# Pg3-Voltage_signal_condtioning.net
KiCad netlist of a schematic drawn in Altium Designer
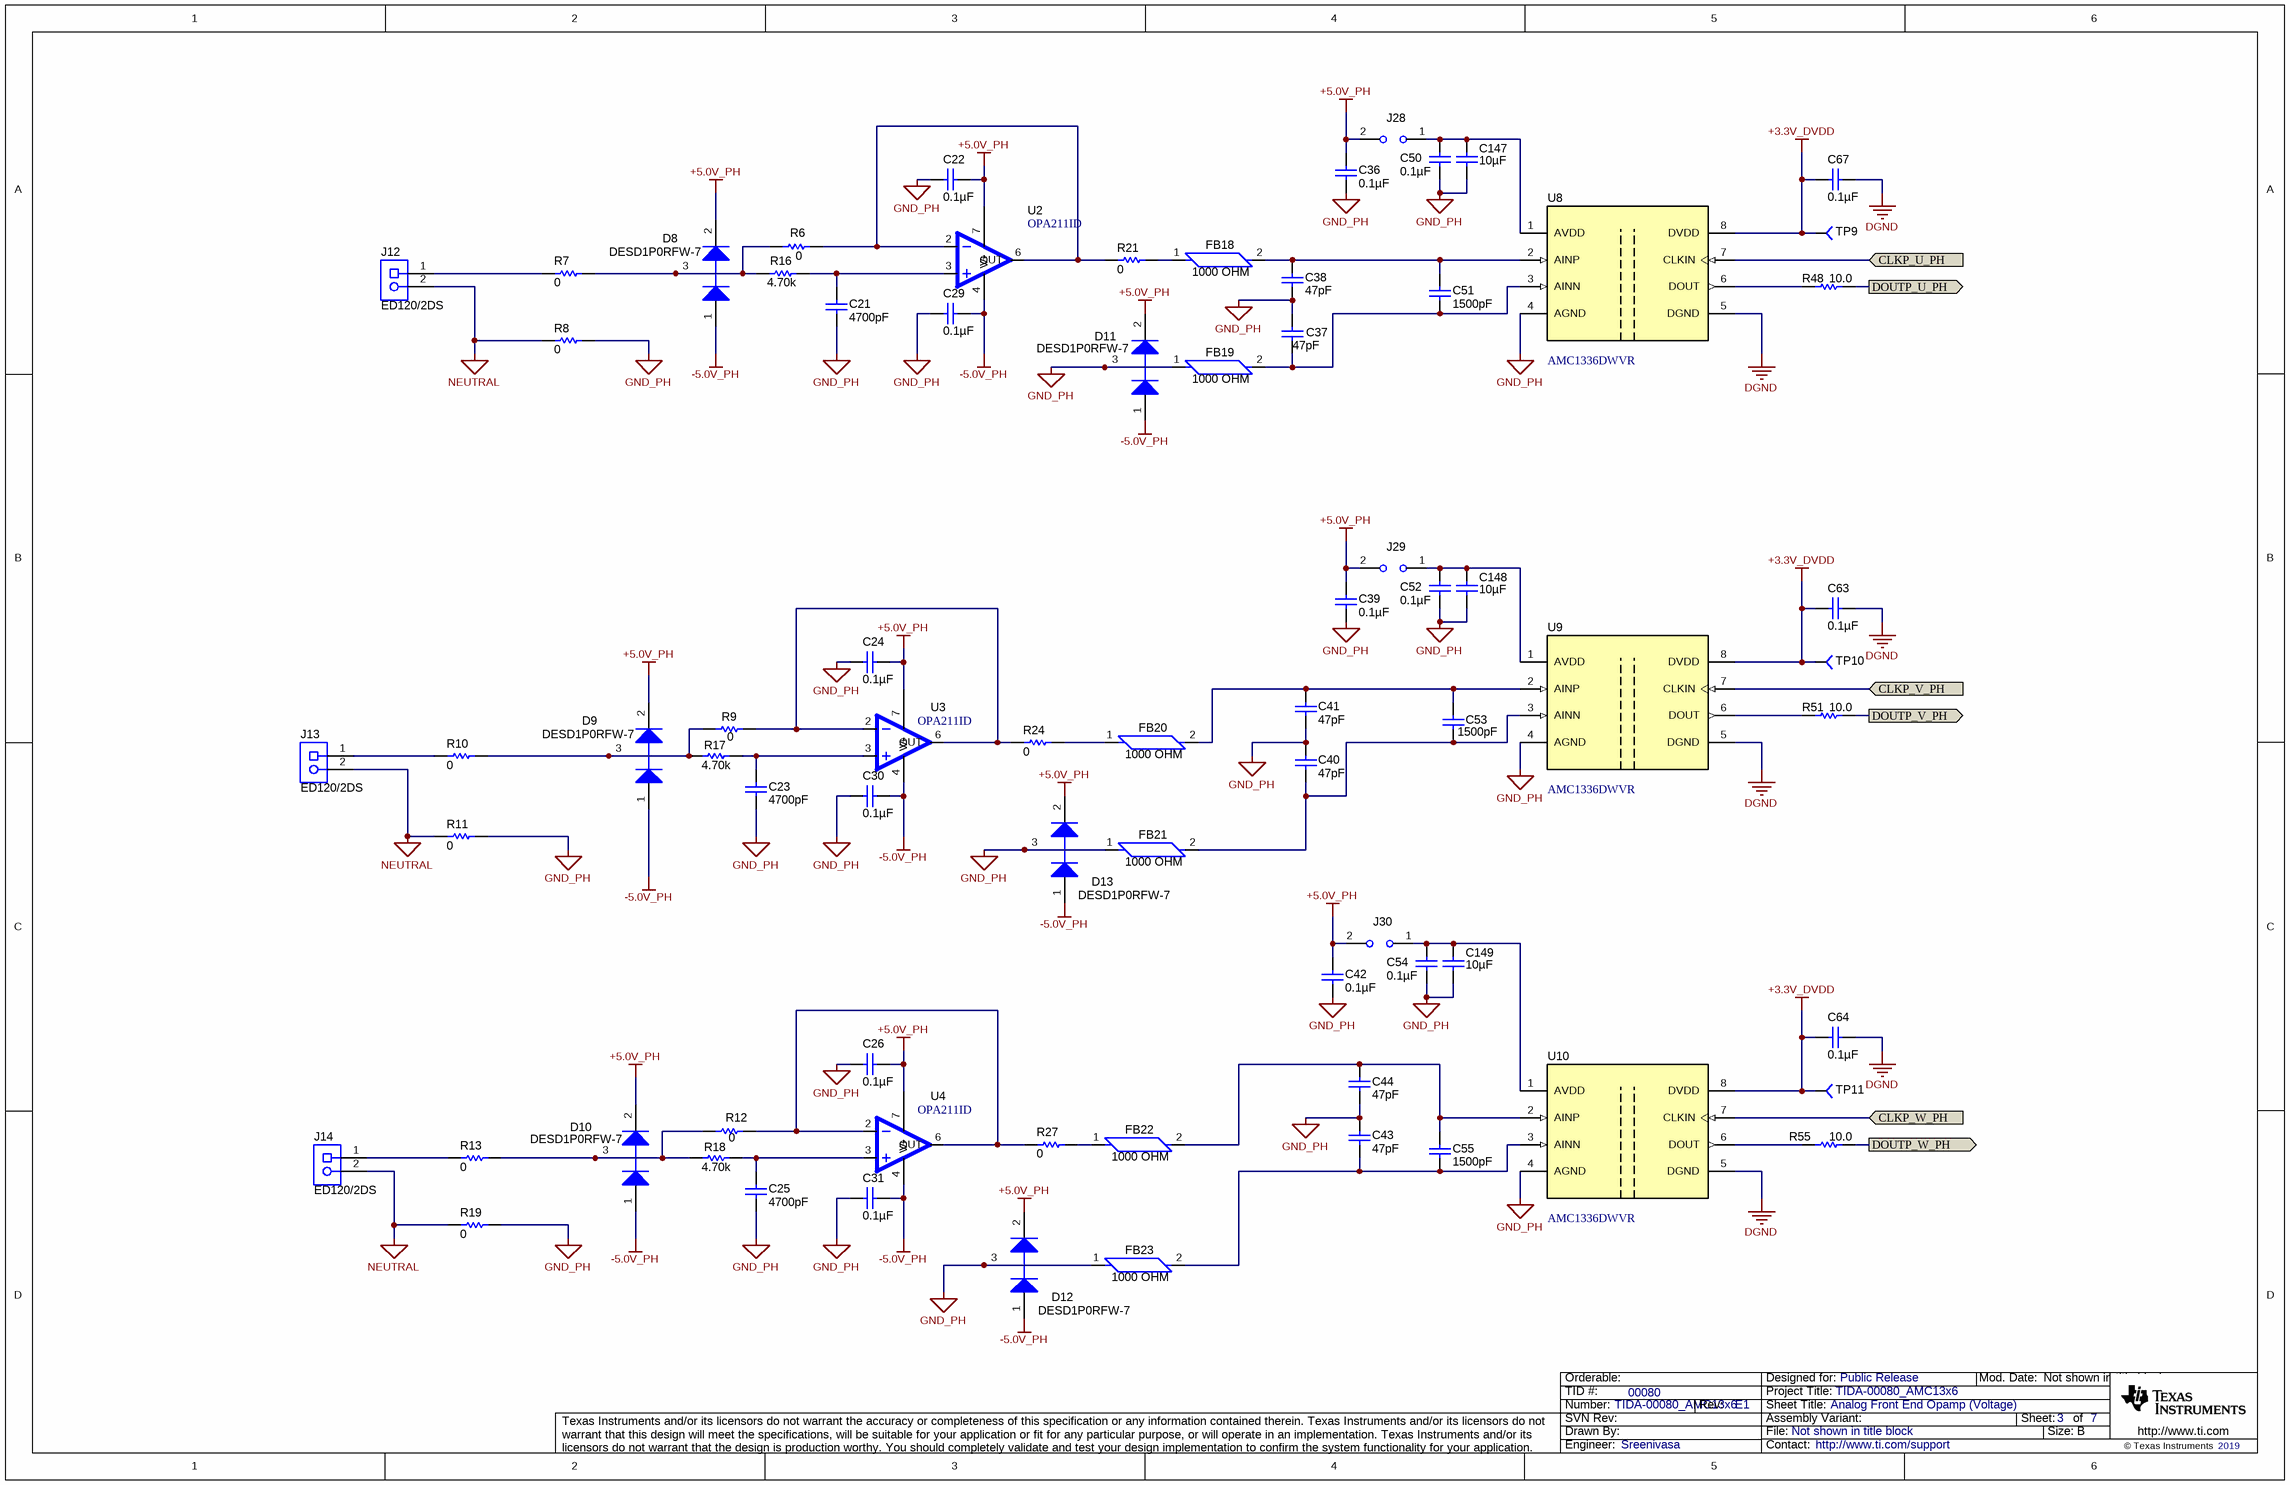
[diagram p0: Pg3-Voltage signal condtioning.SchDoc]

(export (version "E")
  (design (tool "Eeschema 10.0.6"))
  (components
    (comp (ref "C21")
      (value "~")
      (footprint "ISE_MCS_SDM_E1_20MAY:0603")
      (description "CAP, CERM, 4700pF, 100V, +/-10%, X7R, 0603")
      (fields
        (field (name "PARTNUMBER") "06031C472KAT2A")
        (field (name "VALUEDISPLAYED") "4700pF")
        (field (name "MANUFACTURER") "AVX")
        (field (name "PUBLISHER") "Texas Instruments")
      )
      (libsource (lib "Capacitor_Ceramic") (part "06031C472KAT2A"))
    )
    (comp (ref "C22")
      (value "~")
      (footprint "ISE_MCS_SDM_E1_20MAY:0603")
      (description "CAP, CERM, 0.1uF, 50V, +/-10%, X7R, 0603")
      (fields
        (field (name "PARTNUMBER") "C0603C104K5RACTU")
        (field (name "VALUEDISPLAYED") "0.1µF")
        (field (name "MANUFACTURER") "Kemet")
        (field (name "PUBLISHER") "Texas Instruments")
      )
      (libsource (lib "Capacitor_Ceramic") (part "C0603C104K5RACTU"))
    )
    (comp (ref "C23")
      (value "~")
      (footprint "ISE_MCS_SDM_E1_20MAY:0603")
      (description "CAP, CERM, 4700pF, 100V, +/-10%, X7R, 0603")
      (fields
        (field (name "PARTNUMBER") "06031C472KAT2A")
        (field (name "VALUEDISPLAYED") "4700pF")
        (field (name "MANUFACTURER") "AVX")
        (field (name "PUBLISHER") "Texas Instruments")
      )
      (libsource (lib "Capacitor_Ceramic") (part "06031C472KAT2A"))
    )
    (comp (ref "C24")
      (value "~")
      (footprint "ISE_MCS_SDM_E1_20MAY:0603")
      (description "CAP, CERM, 0.1uF, 50V, +/-10%, X7R, 0603")
      (fields
        (field (name "PARTNUMBER") "C0603C104K5RACTU")
        (field (name "VALUEDISPLAYED") "0.1µF")
        (field (name "MANUFACTURER") "Kemet")
        (field (name "PUBLISHER") "Texas Instruments")
      )
      (libsource (lib "Capacitor_Ceramic") (part "C0603C104K5RACTU"))
    )
    (comp (ref "C25")
      (value "~")
      (footprint "ISE_MCS_SDM_E1_20MAY:0603")
      (description "CAP, CERM, 4700pF, 100V, +/-10%, X7R, 0603")
      (fields
        (field (name "PARTNUMBER") "06031C472KAT2A")
        (field (name "VALUEDISPLAYED") "4700pF")
        (field (name "MANUFACTURER") "AVX")
        (field (name "PUBLISHER") "Texas Instruments")
      )
      (libsource (lib "Capacitor_Ceramic") (part "06031C472KAT2A"))
    )
    (comp (ref "C26")
      (value "~")
      (footprint "ISE_MCS_SDM_E1_20MAY:0603")
      (description "CAP, CERM, 0.1uF, 50V, +/-10%, X7R, 0603")
      (fields
        (field (name "PARTNUMBER") "C0603C104K5RACTU")
        (field (name "VALUEDISPLAYED") "0.1µF")
        (field (name "MANUFACTURER") "Kemet")
        (field (name "PUBLISHER") "Texas Instruments")
      )
      (libsource (lib "Capacitor_Ceramic") (part "C0603C104K5RACTU"))
    )
    (comp (ref "C29")
      (value "~")
      (footprint "ISE_MCS_SDM_E1_20MAY:0603")
      (description "CAP, CERM, 0.1uF, 50V, +/-10%, X7R, 0603")
      (fields
        (field (name "PARTNUMBER") "C0603C104K5RACTU")
        (field (name "VALUEDISPLAYED") "0.1µF")
        (field (name "MANUFACTURER") "Kemet")
        (field (name "PUBLISHER") "Texas Instruments")
      )
      (libsource (lib "Capacitor_Ceramic") (part "C0603C104K5RACTU"))
    )
    (comp (ref "C30")
      (value "~")
      (footprint "ISE_MCS_SDM_E1_20MAY:0603")
      (description "CAP, CERM, 0.1uF, 50V, +/-10%, X7R, 0603")
      (fields
        (field (name "PARTNUMBER") "C0603C104K5RACTU")
        (field (name "VALUEDISPLAYED") "0.1µF")
        (field (name "MANUFACTURER") "Kemet")
        (field (name "PUBLISHER") "Texas Instruments")
      )
      (libsource (lib "Capacitor_Ceramic") (part "C0603C104K5RACTU"))
    )
    (comp (ref "C31")
      (value "~")
      (footprint "ISE_MCS_SDM_E1_20MAY:0603")
      (description "CAP, CERM, 0.1uF, 50V, +/-10%, X7R, 0603")
      (fields
        (field (name "PARTNUMBER") "C0603C104K5RACTU")
        (field (name "VALUEDISPLAYED") "0.1µF")
        (field (name "MANUFACTURER") "Kemet")
        (field (name "PUBLISHER") "Texas Instruments")
      )
      (libsource (lib "Capacitor_Ceramic") (part "C0603C104K5RACTU"))
    )
    (comp (ref "C36")
      (value "~")
      (footprint "ISE_MCS_SDM_E1_20MAY:0603")
      (description "CAP, CERM, 0.1uF, 50V, +/-10%, X7R, 0603")
      (fields
        (field (name "PARTNUMBER") "C0603C104K5RACTU")
        (field (name "VALUEDISPLAYED") "0.1µF")
        (field (name "MANUFACTURER") "Kemet")
        (field (name "PUBLISHER") "Texas Instruments")
      )
      (libsource (lib "Capacitor_Ceramic") (part "C0603C104K5RACTU"))
    )
    (comp (ref "C37")
      (value "GRM21A5C2E470JW01D")
      (footprint "ISE_MCS_SDM_E1_20MAY:0805_HV")
      (description "CAP, CERM, 47pF, 500V, +/-5%, C0G/NP0, 0805")
      (fields
        (field (name "VALUEDISPLAYED") "47pF")
        (field (name "MANUFACTURER") "MuRata")
        (field (name "PUBLISHER") "Texas Instruments")
      )
      (libsource (lib "Capacitor_Ceramic") (part "GRM21A5C2E470JW01D"))
    )
    (comp (ref "C38")
      (value "GRM21A5C2E470JW01D")
      (footprint "ISE_MCS_SDM_E1_20MAY:0805_HV")
      (description "CAP, CERM, 47pF, 500V, +/-5%, C0G/NP0, 0805")
      (fields
        (field (name "VALUEDISPLAYED") "47pF")
        (field (name "MANUFACTURER") "MuRata")
        (field (name "PUBLISHER") "Texas Instruments")
      )
      (libsource (lib "Capacitor_Ceramic") (part "GRM21A5C2E470JW01D"))
    )
    (comp (ref "C39")
      (value "~")
      (footprint "ISE_MCS_SDM_E1_20MAY:0603")
      (description "CAP, CERM, 0.1uF, 50V, +/-10%, X7R, 0603")
      (fields
        (field (name "PARTNUMBER") "C0603C104K5RACTU")
        (field (name "VALUEDISPLAYED") "0.1µF")
        (field (name "MANUFACTURER") "Kemet")
        (field (name "PUBLISHER") "Texas Instruments")
      )
      (libsource (lib "Capacitor_Ceramic") (part "C0603C104K5RACTU"))
    )
    (comp (ref "C40")
      (value "GRM21A5C2E470JW01D")
      (footprint "ISE_MCS_SDM_E1_20MAY:0805_HV")
      (description "CAP, CERM, 47pF, 500V, +/-5%, C0G/NP0, 0805")
      (fields
        (field (name "VALUEDISPLAYED") "47pF")
        (field (name "MANUFACTURER") "MuRata")
        (field (name "PUBLISHER") "Texas Instruments")
      )
      (libsource (lib "Capacitor_Ceramic") (part "GRM21A5C2E470JW01D"))
    )
    (comp (ref "C41")
      (value "GRM21A5C2E470JW01D")
      (footprint "ISE_MCS_SDM_E1_20MAY:0805_HV")
      (description "CAP, CERM, 47pF, 500V, +/-5%, C0G/NP0, 0805")
      (fields
        (field (name "VALUEDISPLAYED") "47pF")
        (field (name "MANUFACTURER") "MuRata")
        (field (name "PUBLISHER") "Texas Instruments")
      )
      (libsource (lib "Capacitor_Ceramic") (part "GRM21A5C2E470JW01D"))
    )
    (comp (ref "C42")
      (value "~")
      (footprint "ISE_MCS_SDM_E1_20MAY:0603")
      (description "CAP, CERM, 0.1uF, 50V, +/-10%, X7R, 0603")
      (fields
        (field (name "PARTNUMBER") "C0603C104K5RACTU")
        (field (name "VALUEDISPLAYED") "0.1µF")
        (field (name "MANUFACTURER") "Kemet")
        (field (name "PUBLISHER") "Texas Instruments")
      )
      (libsource (lib "Capacitor_Ceramic") (part "C0603C104K5RACTU"))
    )
    (comp (ref "C43")
      (value "GRM21A5C2E470JW01D")
      (footprint "ISE_MCS_SDM_E1_20MAY:0805_HV")
      (description "CAP, CERM, 47pF, 500V, +/-5%, C0G/NP0, 0805")
      (fields
        (field (name "VALUEDISPLAYED") "47pF")
        (field (name "MANUFACTURER") "MuRata")
        (field (name "PUBLISHER") "Texas Instruments")
      )
      (libsource (lib "Capacitor_Ceramic") (part "GRM21A5C2E470JW01D"))
    )
    (comp (ref "C44")
      (value "GRM21A5C2E470JW01D")
      (footprint "ISE_MCS_SDM_E1_20MAY:0805_HV")
      (description "CAP, CERM, 47pF, 500V, +/-5%, C0G/NP0, 0805")
      (fields
        (field (name "VALUEDISPLAYED") "47pF")
        (field (name "MANUFACTURER") "MuRata")
        (field (name "PUBLISHER") "Texas Instruments")
      )
      (libsource (lib "Capacitor_Ceramic") (part "GRM21A5C2E470JW01D"))
    )
    (comp (ref "C50")
      (value "~")
      (footprint "ISE_MCS_SDM_E1_20MAY:0603")
      (description "CAP, CERM, 0.1uF, 50V, +/-10%, X7R, 0603")
      (fields
        (field (name "PARTNUMBER") "C0603C104K5RACTU")
        (field (name "VALUEDISPLAYED") "0.1µF")
        (field (name "MANUFACTURER") "Kemet")
        (field (name "PUBLISHER") "Texas Instruments")
      )
      (libsource (lib "Capacitor_Ceramic") (part "C0603C104K5RACTU"))
    )
    (comp (ref "C51")
      (value "06031C152KAT2A")
      (footprint "ISE_MCS_SDM_E1_20MAY:0603")
      (description "CAP, CERM, 1500pF, 100V, +/-10%, X7R, 0603")
      (fields
        (field (name "VALUEDISPLAYED") "1500pF")
        (field (name "MANUFACTURER") "AVX")
        (field (name "PUBLISHER") "Texas Instruments")
      )
      (libsource (lib "Capacitor_Ceramic") (part "06031C152KAT2A"))
    )
    (comp (ref "C52")
      (value "~")
      (footprint "ISE_MCS_SDM_E1_20MAY:0603")
      (description "CAP, CERM, 0.1uF, 50V, +/-10%, X7R, 0603")
      (fields
        (field (name "PARTNUMBER") "C0603C104K5RACTU")
        (field (name "VALUEDISPLAYED") "0.1µF")
        (field (name "MANUFACTURER") "Kemet")
        (field (name "PUBLISHER") "Texas Instruments")
      )
      (libsource (lib "Capacitor_Ceramic") (part "C0603C104K5RACTU"))
    )
    (comp (ref "C53")
      (value "06031C152KAT2A")
      (footprint "ISE_MCS_SDM_E1_20MAY:0603")
      (description "CAP, CERM, 1500pF, 100V, +/-10%, X7R, 0603")
      (fields
        (field (name "VALUEDISPLAYED") "1500pF")
        (field (name "MANUFACTURER") "AVX")
        (field (name "PUBLISHER") "Texas Instruments")
      )
      (libsource (lib "Capacitor_Ceramic") (part "06031C152KAT2A"))
    )
    (comp (ref "C54")
      (value "~")
      (footprint "ISE_MCS_SDM_E1_20MAY:0603")
      (description "CAP, CERM, 0.1uF, 50V, +/-10%, X7R, 0603")
      (fields
        (field (name "PARTNUMBER") "C0603C104K5RACTU")
        (field (name "VALUEDISPLAYED") "0.1µF")
        (field (name "MANUFACTURER") "Kemet")
        (field (name "PUBLISHER") "Texas Instruments")
      )
      (libsource (lib "Capacitor_Ceramic") (part "C0603C104K5RACTU"))
    )
    (comp (ref "C55")
      (value "06031C152KAT2A")
      (footprint "ISE_MCS_SDM_E1_20MAY:0603")
      (description "CAP, CERM, 1500pF, 100V, +/-10%, X7R, 0603")
      (fields
        (field (name "VALUEDISPLAYED") "1500pF")
        (field (name "MANUFACTURER") "AVX")
        (field (name "PUBLISHER") "Texas Instruments")
      )
      (libsource (lib "Capacitor_Ceramic") (part "06031C152KAT2A"))
    )
    (comp (ref "C63")
      (value "~")
      (footprint "ISE_MCS_SDM_E1_20MAY:0603")
      (description "CAP, CERM, 0.1uF, 25V, +/-5%, X7R, 0603")
      (fields
        (field (name "PARTNUMBER") "06033C104JAT2A")
        (field (name "VALUEDISPLAYED") "0.1µF")
        (field (name "MANUFACTURER") "AVX")
        (field (name "PUBLISHER") "Texas Instruments")
      )
      (libsource (lib "Capacitor_Ceramic") (part "06033C104JAT2A"))
    )
    (comp (ref "C64")
      (value "~")
      (footprint "ISE_MCS_SDM_E1_20MAY:0603")
      (description "CAP, CERM, 0.1uF, 25V, +/-5%, X7R, 0603")
      (fields
        (field (name "PARTNUMBER") "06033C104JAT2A")
        (field (name "VALUEDISPLAYED") "0.1µF")
        (field (name "MANUFACTURER") "AVX")
        (field (name "PUBLISHER") "Texas Instruments")
      )
      (libsource (lib "Capacitor_Ceramic") (part "06033C104JAT2A"))
    )
    (comp (ref "C67")
      (value "~")
      (footprint "ISE_MCS_SDM_E1_20MAY:0603")
      (description "CAP, CERM, 0.1uF, 25V, +/-5%, X7R, 0603")
      (fields
        (field (name "PARTNUMBER") "06033C104JAT2A")
        (field (name "VALUEDISPLAYED") "0.1µF")
        (field (name "MANUFACTURER") "AVX")
        (field (name "PUBLISHER") "Texas Instruments")
      )
      (libsource (lib "Capacitor_Ceramic") (part "06033C104JAT2A"))
    )
    (comp (ref "C147")
      (value "~")
      (footprint "1210")
      (description "CAP, CERM, 10uF, 35V, +/-20%, X7R, 1210")
      (fields
        (field (name "PARTNUMBER") "GMK325AB7106MM-T")
        (field (name "VALUEDISPLAYED") "10µF")
        (field (name "MANUFACTURER") "Taiyo Yuden")
        (field (name "PUBLISHER") "Texas Instruments")
      )
      (libsource (lib "Capacitor_Ceramic") (part "GMK325AB7106MM-T"))
    )
    (comp (ref "C148")
      (value "~")
      (footprint "1210")
      (description "CAP, CERM, 10uF, 35V, +/-20%, X7R, 1210")
      (fields
        (field (name "PARTNUMBER") "GMK325AB7106MM-T")
        (field (name "VALUEDISPLAYED") "10µF")
        (field (name "MANUFACTURER") "Taiyo Yuden")
        (field (name "PUBLISHER") "Texas Instruments")
      )
      (libsource (lib "Capacitor_Ceramic") (part "GMK325AB7106MM-T"))
    )
    (comp (ref "C149")
      (value "~")
      (footprint "1210")
      (description "CAP, CERM, 10uF, 35V, +/-20%, X7R, 1210")
      (fields
        (field (name "PARTNUMBER") "GMK325AB7106MM-T")
        (field (name "VALUEDISPLAYED") "10µF")
        (field (name "MANUFACTURER") "Taiyo Yuden")
        (field (name "PUBLISHER") "Texas Instruments")
      )
      (libsource (lib "Capacitor_Ceramic") (part "GMK325AB7106MM-T"))
    )
    (comp (ref "D8")
      (value "DESD1P0RFW-7")
      (footprint "ISE_MCS_SDM_E1_20MAY:SOT-323")
      (description "Diode, P-N, 70V, 0.2A, SOT-323")
      (fields (field (name "MANUFACTURER") "Diodes Inc") (field (name "PUBLISHER") "Texas Instruments"))
      (libsource (lib "Diode") (part "BAV99WT1G"))
    )
    (comp (ref "D9")
      (value "DESD1P0RFW-7")
      (footprint "ISE_MCS_SDM_E1_20MAY:SOT-323")
      (description "Diode, P-N, 70V, 0.2A, SOT-323")
      (fields (field (name "MANUFACTURER") "Diodes Inc") (field (name "PUBLISHER") "Texas Instruments"))
      (libsource (lib "Diode") (part "BAV99WT1G"))
    )
    (comp (ref "D10")
      (value "DESD1P0RFW-7")
      (footprint "ISE_MCS_SDM_E1_20MAY:SOT-323")
      (description "Diode, P-N, 70V, 0.2A, SOT-323")
      (fields (field (name "MANUFACTURER") "Diodes Inc") (field (name "PUBLISHER") "Texas Instruments"))
      (libsource (lib "Diode") (part "BAV99WT1G"))
    )
    (comp (ref "D11")
      (value "DESD1P0RFW-7")
      (footprint "SOT-323")
      (description "Diode, P-N, 70V, 0.2A, SOT-323")
      (fields (field (name "MANUFACTURER") "Diodes Inc") (field (name "PUBLISHER") "Texas Instruments"))
      (libsource (lib "Diode") (part "BAV99WT1G"))
    )
    (comp (ref "D12")
      (value "DESD1P0RFW-7")
      (footprint "SOT-323")
      (description "Diode, P-N, 70V, 0.2A, SOT-323")
      (fields (field (name "MANUFACTURER") "Diodes Inc") (field (name "PUBLISHER") "Texas Instruments"))
      (libsource (lib "Diode") (part "BAV99WT1G"))
    )
    (comp (ref "D13")
      (value "DESD1P0RFW-7")
      (footprint "SOT-323")
      (description "Diode, P-N, 70V, 0.2A, SOT-323")
      (fields (field (name "MANUFACTURER") "Diodes Inc") (field (name "PUBLISHER") "Texas Instruments"))
      (libsource (lib "Diode") (part "BAV99WT1G"))
    )
    (comp (ref "FB18")
      (value "1000 OHM")
      (footprint "FB0603")
      (description "FERRITE CHIP 1000 OHM 300MA 0603")
      (fields
        (field (name "PARTNUMBER") "MMZ1608B102C")
        (field (name "MANUFACTURER") "TDK Corporation")
        (field (name "PUBLISHER") "TI")
      )
      (libsource (lib "Isolated current sensing") (part "MMZ1608B102C"))
    )
    (comp (ref "FB19")
      (value "1000 OHM")
      (footprint "FB0603")
      (description "FERRITE CHIP 1000 OHM 300MA 0603")
      (fields
        (field (name "PARTNUMBER") "MMZ1608B102C")
        (field (name "MANUFACTURER") "TDK Corporation")
        (field (name "PUBLISHER") "TI")
      )
      (libsource (lib "Isolated current sensing") (part "MMZ1608B102C"))
    )
    (comp (ref "FB20")
      (value "1000 OHM")
      (footprint "FB0603")
      (description "FERRITE CHIP 1000 OHM 300MA 0603")
      (fields
        (field (name "PARTNUMBER") "MMZ1608B102C")
        (field (name "MANUFACTURER") "TDK Corporation")
        (field (name "PUBLISHER") "TI")
      )
      (libsource (lib "Isolated current sensing") (part "MMZ1608B102C"))
    )
    (comp (ref "FB21")
      (value "1000 OHM")
      (footprint "FB0603")
      (description "FERRITE CHIP 1000 OHM 300MA 0603")
      (fields
        (field (name "PARTNUMBER") "MMZ1608B102C")
        (field (name "MANUFACTURER") "TDK Corporation")
        (field (name "PUBLISHER") "TI")
      )
      (libsource (lib "Isolated current sensing") (part "MMZ1608B102C"))
    )
    (comp (ref "FB22")
      (value "1000 OHM")
      (footprint "FB0603")
      (description "FERRITE CHIP 1000 OHM 300MA 0603")
      (fields
        (field (name "PARTNUMBER") "MMZ1608B102C")
        (field (name "MANUFACTURER") "TDK Corporation")
        (field (name "PUBLISHER") "TI")
      )
      (libsource (lib "Isolated current sensing") (part "MMZ1608B102C"))
    )
    (comp (ref "FB23")
      (value "1000 OHM")
      (footprint "FB0603")
      (description "FERRITE CHIP 1000 OHM 300MA 0603")
      (fields
        (field (name "PARTNUMBER") "MMZ1608B102C")
        (field (name "MANUFACTURER") "TDK Corporation")
        (field (name "PUBLISHER") "TI")
      )
      (libsource (lib "Isolated current sensing") (part "MMZ1608B102C"))
    )
    (comp (ref "J12")
      (value "ED120/2DS")
      (footprint "ISE_MCS_SDM_E1_20MAY:CONN_ED120-2DS")
      (description "TERMINAL BLOCK 5.08MM VERT 2POS, TH")
      (fields
        (field (name "MANUFACTURER") "On-Shore Technology")
        (field (name "SYMBOLCREATOR") "a0412235")
        (field (name "PUBLISHER") "Texas Instruments")
      )
      (libsource (lib "Connectors") (part "ED120/2DS"))
    )
    (comp (ref "J13")
      (value "ED120/2DS")
      (footprint "ISE_MCS_SDM_E1_20MAY:CONN_ED120-2DS")
      (description "TERMINAL BLOCK 5.08MM VERT 2POS, TH")
      (fields
        (field (name "MANUFACTURER") "On-Shore Technology")
        (field (name "SYMBOLCREATOR") "a0412235")
        (field (name "PUBLISHER") "Texas Instruments")
      )
      (libsource (lib "Connectors") (part "ED120/2DS"))
    )
    (comp (ref "J14")
      (value "ED120/2DS")
      (footprint "ISE_MCS_SDM_E1_20MAY:CONN_ED120-2DS")
      (description "TERMINAL BLOCK 5.08MM VERT 2POS, TH")
      (fields
        (field (name "MANUFACTURER") "On-Shore Technology")
        (field (name "SYMBOLCREATOR") "a0412235")
        (field (name "PUBLISHER") "Texas Instruments")
      )
      (libsource (lib "Connectors") (part "ED120/2DS"))
    )
    (comp (ref "J28")
      (value "~")
      (footprint "ISE_MCS_SDM_E1_20MAY:HDR100_1X2")
      (description "Header, Male 2-pin, 100mil spacing,")
      (fields (field (name "MANUFACTURER") "FCI") (field (name "PARTNUMBER") "68001-402HLF"))
      (libsource (lib "PADSlegacy_Hardware") (part "JUMPER_2X100MIL"))
    )
    (comp (ref "J29")
      (value "~")
      (footprint "ISE_MCS_SDM_E1_20MAY:HDR100_1X2")
      (description "Header, Male 2-pin, 100mil spacing,")
      (fields (field (name "MANUFACTURER") "FCI") (field (name "PARTNUMBER") "68001-402HLF"))
      (libsource (lib "PADSlegacy_Hardware") (part "JUMPER_2X100MIL"))
    )
    (comp (ref "J30")
      (value "~")
      (footprint "ISE_MCS_SDM_E1_20MAY:HDR100_1X2")
      (description "Header, Male 2-pin, 100mil spacing,")
      (fields (field (name "MANUFACTURER") "FCI") (field (name "PARTNUMBER") "68001-402HLF"))
      (libsource (lib "PADSlegacy_Hardware") (part "JUMPER_2X100MIL"))
    )
    (comp (ref "R6")
      (value "0")
      (footprint "0603")
      (description "RES, 0 ohm, 5%, 0.1W, 0603")
      (fields
        (field (name "PARTNUMBER") "CRCW06030000Z0EA")
        (field (name "MANUFACTURER") "Vishay-Dale")
        (field (name "PUBLISHER") "Texas Instruments")
      )
      (libsource (lib "Isolated current sensing") (part "CRCW06030000Z0EA"))
    )
    (comp (ref "R7")
      (value "0")
      (footprint "0805_HV")
      (description "RES, 0 ohm, 5%, 0.125W, 0805")
      (fields
        (field (name "PARTNUMBER") "CRCW08050000Z0EA")
        (field (name "MANUFACTURER") "Vishay-Dale")
        (field (name "PUBLISHER") "Texas Instruments")
      )
      (libsource (lib "Resistor_0805") (part "CRCW08050000Z0EA"))
    )
    (comp (ref "R8")
      (value "0")
      (footprint "0805_HV")
      (description "RES, 0 ohm, 5%, 0.125W, 0805")
      (fields
        (field (name "PARTNUMBER") "CRCW08050000Z0EA")
        (field (name "MANUFACTURER") "Vishay-Dale")
        (field (name "PUBLISHER") "Texas Instruments")
      )
      (libsource (lib "Resistor_0805") (part "CRCW08050000Z0EA"))
    )
    (comp (ref "R9")
      (value "0")
      (footprint "0603")
      (description "RES, 0 ohm, 5%, 0.1W, 0603")
      (fields
        (field (name "PARTNUMBER") "CRCW06030000Z0EA")
        (field (name "MANUFACTURER") "Vishay-Dale")
        (field (name "PUBLISHER") "Texas Instruments")
      )
      (libsource (lib "Isolated current sensing") (part "CRCW06030000Z0EA"))
    )
    (comp (ref "R10")
      (value "0")
      (footprint "0805_HV")
      (description "RES, 0 ohm, 5%, 0.125W, 0805")
      (fields
        (field (name "PARTNUMBER") "CRCW08050000Z0EA")
        (field (name "MANUFACTURER") "Vishay-Dale")
        (field (name "PUBLISHER") "Texas Instruments")
      )
      (libsource (lib "Resistor_0805") (part "CRCW08050000Z0EA"))
    )
    (comp (ref "R11")
      (value "0")
      (footprint "0805_HV")
      (description "RES, 0 ohm, 5%, 0.125W, 0805")
      (fields
        (field (name "PARTNUMBER") "CRCW08050000Z0EA")
        (field (name "MANUFACTURER") "Vishay-Dale")
        (field (name "PUBLISHER") "Texas Instruments")
      )
      (libsource (lib "Resistor_0805") (part "CRCW08050000Z0EA"))
    )
    (comp (ref "R12")
      (value "0")
      (footprint "0603")
      (description "RES, 0 ohm, 5%, 0.1W, 0603")
      (fields
        (field (name "PARTNUMBER") "CRCW06030000Z0EA")
        (field (name "MANUFACTURER") "Vishay-Dale")
        (field (name "PUBLISHER") "Texas Instruments")
      )
      (libsource (lib "Isolated current sensing") (part "CRCW06030000Z0EA"))
    )
    (comp (ref "R13")
      (value "0")
      (footprint "0805_HV")
      (description "RES, 0 ohm, 5%, 0.125W, 0805")
      (fields
        (field (name "PARTNUMBER") "CRCW08050000Z0EA")
        (field (name "MANUFACTURER") "Vishay-Dale")
        (field (name "PUBLISHER") "Texas Instruments")
      )
      (libsource (lib "Resistor_0805") (part "CRCW08050000Z0EA"))
    )
    (comp (ref "R16")
      (value "4.70k")
      (footprint "ISE_MCS_SDM_E1_20MAY:0603")
      (description "RES, 4.70k ohm, 1%, 0.1W, 0603")
      (fields
        (field (name "PARTNUMBER") "RC0603FR-074K7L")
        (field (name "MANUFACTURER") "Yageo America")
        (field (name "PUBLISHER") "Texas Instruments")
      )
      (libsource (lib "Resistor_0603") (part "RC0603FR-074K7L"))
    )
    (comp (ref "R17")
      (value "4.70k")
      (footprint "ISE_MCS_SDM_E1_20MAY:0603")
      (description "RES, 4.70k ohm, 1%, 0.1W, 0603")
      (fields
        (field (name "PARTNUMBER") "RC0603FR-074K7L")
        (field (name "MANUFACTURER") "Yageo America")
        (field (name "PUBLISHER") "Texas Instruments")
      )
      (libsource (lib "Resistor_0603") (part "RC0603FR-074K7L"))
    )
    (comp (ref "R18")
      (value "4.70k")
      (footprint "ISE_MCS_SDM_E1_20MAY:0603")
      (description "RES, 4.70k ohm, 1%, 0.1W, 0603")
      (fields
        (field (name "PARTNUMBER") "RC0603FR-074K7L")
        (field (name "MANUFACTURER") "Yageo America")
        (field (name "PUBLISHER") "Texas Instruments")
      )
      (libsource (lib "Resistor_0603") (part "RC0603FR-074K7L"))
    )
    (comp (ref "R19")
      (value "0")
      (footprint "0805_HV")
      (description "RES, 0 ohm, 5%, 0.125W, 0805")
      (fields
        (field (name "PARTNUMBER") "CRCW08050000Z0EA")
        (field (name "MANUFACTURER") "Vishay-Dale")
        (field (name "PUBLISHER") "Texas Instruments")
      )
      (libsource (lib "Resistor_0805") (part "CRCW08050000Z0EA"))
    )
    (comp (ref "R21")
      (value "0")
      (footprint "ISE_MCS_SDM_E1_20MAY:0603")
      (description "RES, 0 ohm, 5%, 0.1W, 0603")
      (fields
        (field (name "PARTNUMBER") "CRCW06030000Z0EA")
        (field (name "MANUFACTURER") "Vishay-Dale")
        (field (name "PUBLISHER") "Texas Instruments")
      )
      (libsource (lib "Resistor_0603") (part "CRCW06030000Z0EA"))
    )
    (comp (ref "R24")
      (value "0")
      (footprint "ISE_MCS_SDM_E1_20MAY:0603")
      (description "RES, 0 ohm, 5%, 0.1W, 0603")
      (fields
        (field (name "PARTNUMBER") "CRCW06030000Z0EA")
        (field (name "MANUFACTURER") "Vishay-Dale")
        (field (name "PUBLISHER") "Texas Instruments")
      )
      (libsource (lib "Resistor_0603") (part "CRCW06030000Z0EA"))
    )
    (comp (ref "R27")
      (value "0")
      (footprint "ISE_MCS_SDM_E1_20MAY:0603")
      (description "RES, 0 ohm, 5%, 0.1W, 0603")
      (fields
        (field (name "PARTNUMBER") "CRCW06030000Z0EA")
        (field (name "MANUFACTURER") "Vishay-Dale")
        (field (name "PUBLISHER") "Texas Instruments")
      )
      (libsource (lib "Resistor_0603") (part "CRCW06030000Z0EA"))
    )
    (comp (ref "R48")
      (value "10.0")
      (footprint "ISE_MCS_SDM_E1_20MAY:0603")
      (description "RES, 10.0 ohm, 1%, 0.1W, 0603")
      (fields
        (field (name "PARTNUMBER") "CRCW060310R0FKEA")
        (field (name "MANUFACTURER") "Vishay-Dale")
        (field (name "PUBLISHER") "Texas Instruments")
      )
      (libsource (lib "Resistor_0603") (part "CRCW060310R0FKEA"))
    )
    (comp (ref "R51")
      (value "10.0")
      (footprint "ISE_MCS_SDM_E1_20MAY:0603")
      (description "RES, 10.0 ohm, 1%, 0.1W, 0603")
      (fields
        (field (name "PARTNUMBER") "CRCW060310R0FKEA")
        (field (name "MANUFACTURER") "Vishay-Dale")
        (field (name "PUBLISHER") "Texas Instruments")
      )
      (libsource (lib "Resistor_0603") (part "CRCW060310R0FKEA"))
    )
    (comp (ref "R55")
      (value "10.0")
      (footprint "ISE_MCS_SDM_E1_20MAY:0603")
      (description "RES, 10.0 ohm, 1%, 0.1W, 0603")
      (fields
        (field (name "PARTNUMBER") "CRCW060310R0FKEA")
        (field (name "MANUFACTURER") "Vishay-Dale")
        (field (name "PUBLISHER") "Texas Instruments")
      )
      (libsource (lib "Resistor_0603") (part "CRCW060310R0FKEA"))
    )
    (comp (ref "TP9")
      (value "~")
      (footprint "ISE_MCS_SDM_E1_20MAY:TP-040_RND")
      (description "Test Point, O.040 Hole")
      (fields (field (name "MANUFACTURER") "STD"))
      (libsource (lib "PADSlegacy_Hardware") (part "TP-040_RND"))
    )
    (comp (ref "TP10")
      (value "~")
      (footprint "ISE_MCS_SDM_E1_20MAY:TP-040_RND")
      (description "Test Point, O.040 Hole")
      (fields (field (name "MANUFACTURER") "STD"))
      (libsource (lib "PADSlegacy_Hardware") (part "TP-040_RND"))
    )
    (comp (ref "TP11")
      (value "~")
      (footprint "ISE_MCS_SDM_E1_20MAY:TP-040_RND")
      (description "Test Point, O.040 Hole")
      (fields (field (name "MANUFACTURER") "STD"))
      (libsource (lib "PADSlegacy_Hardware") (part "TP-040_RND"))
    )
    (comp (ref "U2")
      (value "OPA211ID")
      (footprint "ISE_MCS_SDM_E1_20MAY:SO8")
      (description "IC, 1.1nV/vHz Noise, Low Power, Precision OpAmp")
      (fields (field (name "MANUFACTURER") "Texas Instruments"))
      (libsource (lib "PADSlegacy_Active") (part "OPA211AID"))
    )
    (comp (ref "U3")
      (value "OPA211ID")
      (footprint "ISE_MCS_SDM_E1_20MAY:SO8")
      (description "IC, 1.1nV/vHz Noise, Low Power, Precision OpAmp")
      (fields (field (name "MANUFACTURER") "Texas Instruments"))
      (libsource (lib "PADSlegacy_Active") (part "OPA211AID"))
    )
    (comp (ref "U4")
      (value "OPA211ID")
      (footprint "ISE_MCS_SDM_E1_20MAY:SO8")
      (description "IC, 1.1nV/vHz Noise, Low Power, Precision OpAmp")
      (fields (field (name "MANUFACTURER") "Texas Instruments"))
      (libsource (lib "PADSlegacy_Active") (part "OPA211AID"))
    )
    (comp (ref "U8")
      (value "AMC1336DWVR")
      (footprint "DWV0008A")
      (fields
        (field (name "MANUFACTURER") "Texas Instruments")
        (field (name "ALTERNATE PARTNUMBER") "AMC1336DWV")
        (field (name "PARTNUMBER") "AMC1336DWVR")
      )
      (libsource (lib "Altium Vault - TI") (part "AMC1306x"))
    )
    (comp (ref "U9")
      (value "AMC1336DWVR")
      (footprint "DWV0008A")
      (fields
        (field (name "MANUFACTURER") "Texas Instruments")
        (field (name "ALTERNATE PARTNUMBER") "AMC1336DWV")
        (field (name "PARTNUMBER") "AMC1336DWVR")
      )
      (libsource (lib "Altium Vault - TI") (part "AMC1306x"))
    )
    (comp (ref "U10")
      (value "AMC1336DWVR")
      (footprint "DWV0008A")
      (fields
        (field (name "MANUFACTURER") "Texas Instruments")
        (field (name "ALTERNATE PARTNUMBER") "AMC1336DWV")
        (field (name "PARTNUMBER") "AMC1336DWVR")
      )
      (libsource (lib "Altium Vault - TI") (part "AMC1306x"))
    )
  )
  (nets
    (net (code "1") (name "+3.3V_DVDD") (class "Default")
      (node (ref "C63") (pin "2") (pinfunction "2_2") (pintype "passive"))
      (node (ref "C64") (pin "2") (pinfunction "2_2") (pintype "passive"))
      (node (ref "C67") (pin "2") (pinfunction "2_2") (pintype "passive"))
      (node (ref "TP10") (pin "1") (pinfunction "1_1") (pintype "passive"))
      (node (ref "TP11") (pin "1") (pinfunction "1_1") (pintype "passive"))
      (node (ref "TP9") (pin "1") (pinfunction "1_1") (pintype "passive"))
      (node (ref "U10") (pin "8") (pinfunction "DVDD_8") (pintype "power_in"))
      (node (ref "U8") (pin "8") (pinfunction "DVDD_8") (pintype "power_in"))
      (node (ref "U9") (pin "8") (pinfunction "DVDD_8") (pintype "power_in"))
    )
    (net (code "2") (name "+5.0V_PH") (class "Default")
      (node (ref "C22") (pin "2") (pinfunction "2_2") (pintype "passive"))
      (node (ref "C24") (pin "2") (pinfunction "2_2") (pintype "passive"))
      (node (ref "C26") (pin "2") (pinfunction "2_2") (pintype "passive"))
      (node (ref "C36") (pin "1") (pinfunction "1_1") (pintype "passive"))
      (node (ref "C39") (pin "1") (pinfunction "1_1") (pintype "passive"))
      (node (ref "C42") (pin "1") (pinfunction "1_1") (pintype "passive"))
      (node (ref "D10") (pin "2") (pinfunction "K_2") (pintype "passive"))
      (node (ref "D11") (pin "2") (pinfunction "K_2") (pintype "passive"))
      (node (ref "D12") (pin "2") (pinfunction "K_2") (pintype "passive"))
      (node (ref "D13") (pin "2") (pinfunction "K_2") (pintype "passive"))
      (node (ref "D8") (pin "2") (pinfunction "K_2") (pintype "passive"))
      (node (ref "D9") (pin "2") (pinfunction "K_2") (pintype "passive"))
      (node (ref "J28") (pin "2") (pintype "passive"))
      (node (ref "J29") (pin "2") (pintype "passive"))
      (node (ref "J30") (pin "2") (pintype "passive"))
      (node (ref "U2") (pin "7") (pinfunction "V+_7") (pintype "passive"))
      (node (ref "U3") (pin "7") (pinfunction "V+_7") (pintype "passive"))
      (node (ref "U4") (pin "7") (pinfunction "V+_7") (pintype "passive"))
    )
    (net (code "3") (name "-5.0V_PH") (class "Default")
      (node (ref "C29") (pin "2") (pinfunction "2_2") (pintype "passive"))
      (node (ref "C30") (pin "2") (pinfunction "2_2") (pintype "passive"))
      (node (ref "C31") (pin "2") (pinfunction "2_2") (pintype "passive"))
      (node (ref "D10") (pin "1") (pinfunction "A_1") (pintype "passive"))
      (node (ref "D11") (pin "1") (pinfunction "A_1") (pintype "passive"))
      (node (ref "D12") (pin "1") (pinfunction "A_1") (pintype "passive"))
      (node (ref "D13") (pin "1") (pinfunction "A_1") (pintype "passive"))
      (node (ref "D8") (pin "1") (pinfunction "A_1") (pintype "passive"))
      (node (ref "D9") (pin "1") (pinfunction "A_1") (pintype "passive"))
      (node (ref "U2") (pin "4") (pinfunction "V-_4") (pintype "passive"))
      (node (ref "U3") (pin "4") (pinfunction "V-_4") (pintype "passive"))
      (node (ref "U4") (pin "4") (pinfunction "V-_4") (pintype "passive"))
    )
    (net (code "4") (name "/CLKP_U_PH") (class "Default")
      (node (ref "U8") (pin "7") (pinfunction "CLKIN_7") (pintype "input"))
    )
    (net (code "5") (name "/CLKP_V_PH") (class "Default")
      (node (ref "U9") (pin "7") (pinfunction "CLKIN_7") (pintype "input"))
    )
    (net (code "6") (name "/CLKP_W_PH") (class "Default")
      (node (ref "U10") (pin "7") (pinfunction "CLKIN_7") (pintype "input"))
    )
    (net (code "7") (name "/DOUTP_U_PH") (class "Default")
      (node (ref "R48") (pin "2") (pinfunction "2_2") (pintype "passive"))
    )
    (net (code "8") (name "/DOUTP_V_PH") (class "Default")
      (node (ref "R51") (pin "2") (pinfunction "2_2") (pintype "passive"))
    )
    (net (code "9") (name "/DOUTP_W_PH") (class "Default")
      (node (ref "R55") (pin "2") (pinfunction "2_2") (pintype "passive"))
    )
    (net (code "10") (name "DGND") (class "Default")
      (node (ref "C63") (pin "1") (pinfunction "1_1") (pintype "passive"))
      (node (ref "C64") (pin "1") (pinfunction "1_1") (pintype "passive"))
      (node (ref "C67") (pin "1") (pinfunction "1_1") (pintype "passive"))
      (node (ref "U10") (pin "5") (pinfunction "DGND_5") (pintype "power_in"))
      (node (ref "U8") (pin "5") (pinfunction "DGND_5") (pintype "power_in"))
      (node (ref "U9") (pin "5") (pinfunction "DGND_5") (pintype "power_in"))
    )
    (net (code "11") (name "GND_PH") (class "Default")
      (node (ref "C147") (pin "1") (pinfunction "1_1") (pintype "passive"))
      (node (ref "C148") (pin "1") (pinfunction "1_1") (pintype "passive"))
      (node (ref "C149") (pin "1") (pinfunction "1_1") (pintype "passive"))
      (node (ref "C21") (pin "2") (pinfunction "2_2") (pintype "passive"))
      (node (ref "C22") (pin "1") (pinfunction "1_1") (pintype "passive"))
      (node (ref "C23") (pin "2") (pinfunction "2_2") (pintype "passive"))
      (node (ref "C24") (pin "1") (pinfunction "1_1") (pintype "passive"))
      (node (ref "C25") (pin "2") (pinfunction "2_2") (pintype "passive"))
      (node (ref "C26") (pin "1") (pinfunction "1_1") (pintype "passive"))
      (node (ref "C29") (pin "1") (pinfunction "1_1") (pintype "passive"))
      (node (ref "C30") (pin "1") (pinfunction "1_1") (pintype "passive"))
      (node (ref "C31") (pin "1") (pinfunction "1_1") (pintype "passive"))
      (node (ref "C36") (pin "2") (pinfunction "2_2") (pintype "passive"))
      (node (ref "C37") (pin "1") (pinfunction "1_1") (pintype "passive"))
      (node (ref "C38") (pin "1") (pinfunction "1_1") (pintype "passive"))
      (node (ref "C39") (pin "2") (pinfunction "2_2") (pintype "passive"))
      (node (ref "C40") (pin "1") (pinfunction "1_1") (pintype "passive"))
      (node (ref "C41") (pin "1") (pinfunction "1_1") (pintype "passive"))
      (node (ref "C42") (pin "2") (pinfunction "2_2") (pintype "passive"))
      (node (ref "C43") (pin "1") (pinfunction "1_1") (pintype "passive"))
      (node (ref "C44") (pin "1") (pinfunction "1_1") (pintype "passive"))
      (node (ref "C50") (pin "2") (pinfunction "2_2") (pintype "passive"))
      (node (ref "C52") (pin "2") (pinfunction "2_2") (pintype "passive"))
      (node (ref "C54") (pin "2") (pinfunction "2_2") (pintype "passive"))
      (node (ref "D11") (pin "3") (pinfunction "C_3") (pintype "passive"))
      (node (ref "D12") (pin "3") (pinfunction "C_3") (pintype "passive"))
      (node (ref "D13") (pin "3") (pinfunction "C_3") (pintype "passive"))
      (node (ref "FB19") (pin "1") (pinfunction "1_1") (pintype "passive"))
      (node (ref "FB21") (pin "1") (pinfunction "1_1") (pintype "passive"))
      (node (ref "FB23") (pin "1") (pinfunction "1_1") (pintype "passive"))
      (node (ref "R11") (pin "2") (pinfunction "2_2") (pintype "passive"))
      (node (ref "R19") (pin "2") (pinfunction "2_2") (pintype "passive"))
      (node (ref "R8") (pin "2") (pinfunction "2_2") (pintype "passive"))
      (node (ref "U10") (pin "4") (pinfunction "AGND_4") (pintype "power_in"))
      (node (ref "U8") (pin "4") (pinfunction "AGND_4") (pintype "power_in"))
      (node (ref "U9") (pin "4") (pinfunction "AGND_4") (pintype "power_in"))
    )
    (net (code "12") (name "NEUTRAL") (class "Default")
      (node (ref "J12") (pin "2") (pinfunction "2_2") (pintype "passive"))
      (node (ref "J13") (pin "2") (pinfunction "2_2") (pintype "passive"))
      (node (ref "J14") (pin "2") (pinfunction "2_2") (pintype "passive"))
      (node (ref "R11") (pin "1") (pinfunction "1_1") (pintype "passive"))
      (node (ref "R19") (pin "1") (pinfunction "1_1") (pintype "passive"))
      (node (ref "R8") (pin "1") (pinfunction "1_1") (pintype "passive"))
    )
    (net (code "13") (name "Net-(C21-Pad1)") (class "Default")
      (node (ref "C21") (pin "1") (pinfunction "1_1") (pintype "passive"))
      (node (ref "R16") (pin "2") (pinfunction "2_2") (pintype "passive"))
      (node (ref "U2") (pin "3") (pintype "passive"))
    )
    (net (code "14") (name "Net-(C23-Pad1)") (class "Default")
      (node (ref "C23") (pin "1") (pinfunction "1_1") (pintype "passive"))
      (node (ref "R17") (pin "2") (pinfunction "2_2") (pintype "passive"))
      (node (ref "U3") (pin "3") (pintype "passive"))
    )
    (net (code "15") (name "Net-(C25-Pad1)") (class "Default")
      (node (ref "C25") (pin "1") (pinfunction "1_1") (pintype "passive"))
      (node (ref "R18") (pin "2") (pinfunction "2_2") (pintype "passive"))
      (node (ref "U4") (pin "3") (pintype "passive"))
    )
    (net (code "16") (name "Net-(D8-C)") (class "Default")
      (node (ref "D8") (pin "3") (pinfunction "C_3") (pintype "passive"))
      (node (ref "R16") (pin "1") (pinfunction "1_1") (pintype "passive"))
      (node (ref "R6") (pin "1") (pinfunction "1_1") (pintype "passive"))
      (node (ref "R7") (pin "2") (pinfunction "2_2") (pintype "passive"))
    )
    (net (code "17") (name "Net-(D9-C)") (class "Default")
      (node (ref "D9") (pin "3") (pinfunction "C_3") (pintype "passive"))
      (node (ref "R10") (pin "2") (pinfunction "2_2") (pintype "passive"))
      (node (ref "R17") (pin "1") (pinfunction "1_1") (pintype "passive"))
      (node (ref "R9") (pin "1") (pinfunction "1_1") (pintype "passive"))
    )
    (net (code "18") (name "Net-(D10-C)") (class "Default")
      (node (ref "D10") (pin "3") (pinfunction "C_3") (pintype "passive"))
      (node (ref "R12") (pin "1") (pinfunction "1_1") (pintype "passive"))
      (node (ref "R13") (pin "2") (pinfunction "2_2") (pintype "passive"))
      (node (ref "R18") (pin "1") (pinfunction "1_1") (pintype "passive"))
    )
    (net (code "19") (name "Net-(FB18-Pad1)") (class "Default")
      (node (ref "FB18") (pin "1") (pinfunction "1_1") (pintype "passive"))
      (node (ref "R21") (pin "2") (pinfunction "2_2") (pintype "passive"))
    )
    (net (code "20") (name "Net-(FB20-Pad1)") (class "Default")
      (node (ref "FB20") (pin "1") (pinfunction "1_1") (pintype "passive"))
      (node (ref "R24") (pin "2") (pinfunction "2_2") (pintype "passive"))
    )
    (net (code "21") (name "Net-(FB22-Pad1)") (class "Default")
      (node (ref "FB22") (pin "1") (pinfunction "1_1") (pintype "passive"))
      (node (ref "R27") (pin "2") (pinfunction "2_2") (pintype "passive"))
    )
    (net (code "22") (name "Net-(J12-Pad1)") (class "Default")
      (node (ref "J12") (pin "1") (pinfunction "1_1") (pintype "passive"))
      (node (ref "R7") (pin "1") (pinfunction "1_1") (pintype "passive"))
    )
    (net (code "23") (name "Net-(J13-Pad1)") (class "Default")
      (node (ref "J13") (pin "1") (pinfunction "1_1") (pintype "passive"))
      (node (ref "R10") (pin "1") (pinfunction "1_1") (pintype "passive"))
    )
    (net (code "24") (name "Net-(J14-Pad1)") (class "Default")
      (node (ref "J14") (pin "1") (pinfunction "1_1") (pintype "passive"))
      (node (ref "R13") (pin "1") (pinfunction "1_1") (pintype "passive"))
    )
    (net (code "25") (name "Net-(U2-OUT)") (class "Default")
      (node (ref "R21") (pin "1") (pinfunction "1_1") (pintype "passive"))
      (node (ref "R6") (pin "2") (pinfunction "2_2") (pintype "passive"))
      (node (ref "U2") (pin "2") (pintype "passive"))
      (node (ref "U2") (pin "6") (pinfunction "OUT_6") (pintype "passive"))
    )
    (net (code "26") (name "Net-(U3-OUT)") (class "Default")
      (node (ref "R24") (pin "1") (pinfunction "1_1") (pintype "passive"))
      (node (ref "R9") (pin "2") (pinfunction "2_2") (pintype "passive"))
      (node (ref "U3") (pin "2") (pintype "passive"))
      (node (ref "U3") (pin "6") (pinfunction "OUT_6") (pintype "passive"))
    )
    (net (code "27") (name "Net-(U4-OUT)") (class "Default")
      (node (ref "R12") (pin "2") (pinfunction "2_2") (pintype "passive"))
      (node (ref "R27") (pin "1") (pinfunction "1_1") (pintype "passive"))
      (node (ref "U4") (pin "2") (pintype "passive"))
      (node (ref "U4") (pin "6") (pinfunction "OUT_6") (pintype "passive"))
    )
    (net (code "28") (name "Net-(U8-AINN)") (class "Default")
      (node (ref "C37") (pin "2") (pinfunction "2_2") (pintype "passive"))
      (node (ref "C51") (pin "2") (pinfunction "2_2") (pintype "passive"))
      (node (ref "FB19") (pin "2") (pinfunction "2_2") (pintype "passive"))
      (node (ref "U8") (pin "3") (pinfunction "AINN_3") (pintype "input"))
    )
    (net (code "29") (name "Net-(U8-AINP)") (class "Default")
      (node (ref "C38") (pin "2") (pinfunction "2_2") (pintype "passive"))
      (node (ref "C51") (pin "1") (pinfunction "1_1") (pintype "passive"))
      (node (ref "FB18") (pin "2") (pinfunction "2_2") (pintype "passive"))
      (node (ref "U8") (pin "2") (pinfunction "AINP_2") (pintype "input"))
    )
    (net (code "30") (name "Net-(U8-AVDD)") (class "Default")
      (node (ref "C147") (pin "2") (pinfunction "2_2") (pintype "passive"))
      (node (ref "C50") (pin "1") (pinfunction "1_1") (pintype "passive"))
      (node (ref "J28") (pin "1") (pintype "passive"))
      (node (ref "U8") (pin "1") (pinfunction "AVDD_1") (pintype "power_in"))
    )
    (net (code "31") (name "Net-(U8-DOUT)") (class "Default")
      (node (ref "R48") (pin "1") (pinfunction "1_1") (pintype "passive"))
      (node (ref "U8") (pin "6") (pinfunction "DOUT_6") (pintype "output"))
    )
    (net (code "32") (name "Net-(U9-AINN)") (class "Default")
      (node (ref "C40") (pin "2") (pinfunction "2_2") (pintype "passive"))
      (node (ref "C53") (pin "2") (pinfunction "2_2") (pintype "passive"))
      (node (ref "FB21") (pin "2") (pinfunction "2_2") (pintype "passive"))
      (node (ref "U9") (pin "3") (pinfunction "AINN_3") (pintype "input"))
    )
    (net (code "33") (name "Net-(U9-AINP)") (class "Default")
      (node (ref "C41") (pin "2") (pinfunction "2_2") (pintype "passive"))
      (node (ref "C53") (pin "1") (pinfunction "1_1") (pintype "passive"))
      (node (ref "FB20") (pin "2") (pinfunction "2_2") (pintype "passive"))
      (node (ref "U9") (pin "2") (pinfunction "AINP_2") (pintype "input"))
    )
    (net (code "34") (name "Net-(U9-AVDD)") (class "Default")
      (node (ref "C148") (pin "2") (pinfunction "2_2") (pintype "passive"))
      (node (ref "C52") (pin "1") (pinfunction "1_1") (pintype "passive"))
      (node (ref "J29") (pin "1") (pintype "passive"))
      (node (ref "U9") (pin "1") (pinfunction "AVDD_1") (pintype "power_in"))
    )
    (net (code "35") (name "Net-(U9-DOUT)") (class "Default")
      (node (ref "R51") (pin "1") (pinfunction "1_1") (pintype "passive"))
      (node (ref "U9") (pin "6") (pinfunction "DOUT_6") (pintype "output"))
    )
    (net (code "36") (name "Net-(U10-AINN)") (class "Default")
      (node (ref "C43") (pin "2") (pinfunction "2_2") (pintype "passive"))
      (node (ref "C55") (pin "2") (pinfunction "2_2") (pintype "passive"))
      (node (ref "FB23") (pin "2") (pinfunction "2_2") (pintype "passive"))
      (node (ref "U10") (pin "3") (pinfunction "AINN_3") (pintype "input"))
    )
    (net (code "37") (name "Net-(U10-AINP)") (class "Default")
      (node (ref "C44") (pin "2") (pinfunction "2_2") (pintype "passive"))
      (node (ref "C55") (pin "1") (pinfunction "1_1") (pintype "passive"))
      (node (ref "FB22") (pin "2") (pinfunction "2_2") (pintype "passive"))
      (node (ref "U10") (pin "2") (pinfunction "AINP_2") (pintype "input"))
    )
    (net (code "38") (name "Net-(U10-AVDD)") (class "Default")
      (node (ref "C149") (pin "2") (pinfunction "2_2") (pintype "passive"))
      (node (ref "C54") (pin "1") (pinfunction "1_1") (pintype "passive"))
      (node (ref "J30") (pin "1") (pintype "passive"))
      (node (ref "U10") (pin "1") (pinfunction "AVDD_1") (pintype "power_in"))
    )
    (net (code "39") (name "Net-(U10-DOUT)") (class "Default")
      (node (ref "R55") (pin "1") (pinfunction "1_1") (pintype "passive"))
      (node (ref "U10") (pin "6") (pinfunction "DOUT_6") (pintype "output"))
    )
  )
)
